# CitizenBoard_V3_2.net
KiCad netlist of a schematic drawn in EAGLE
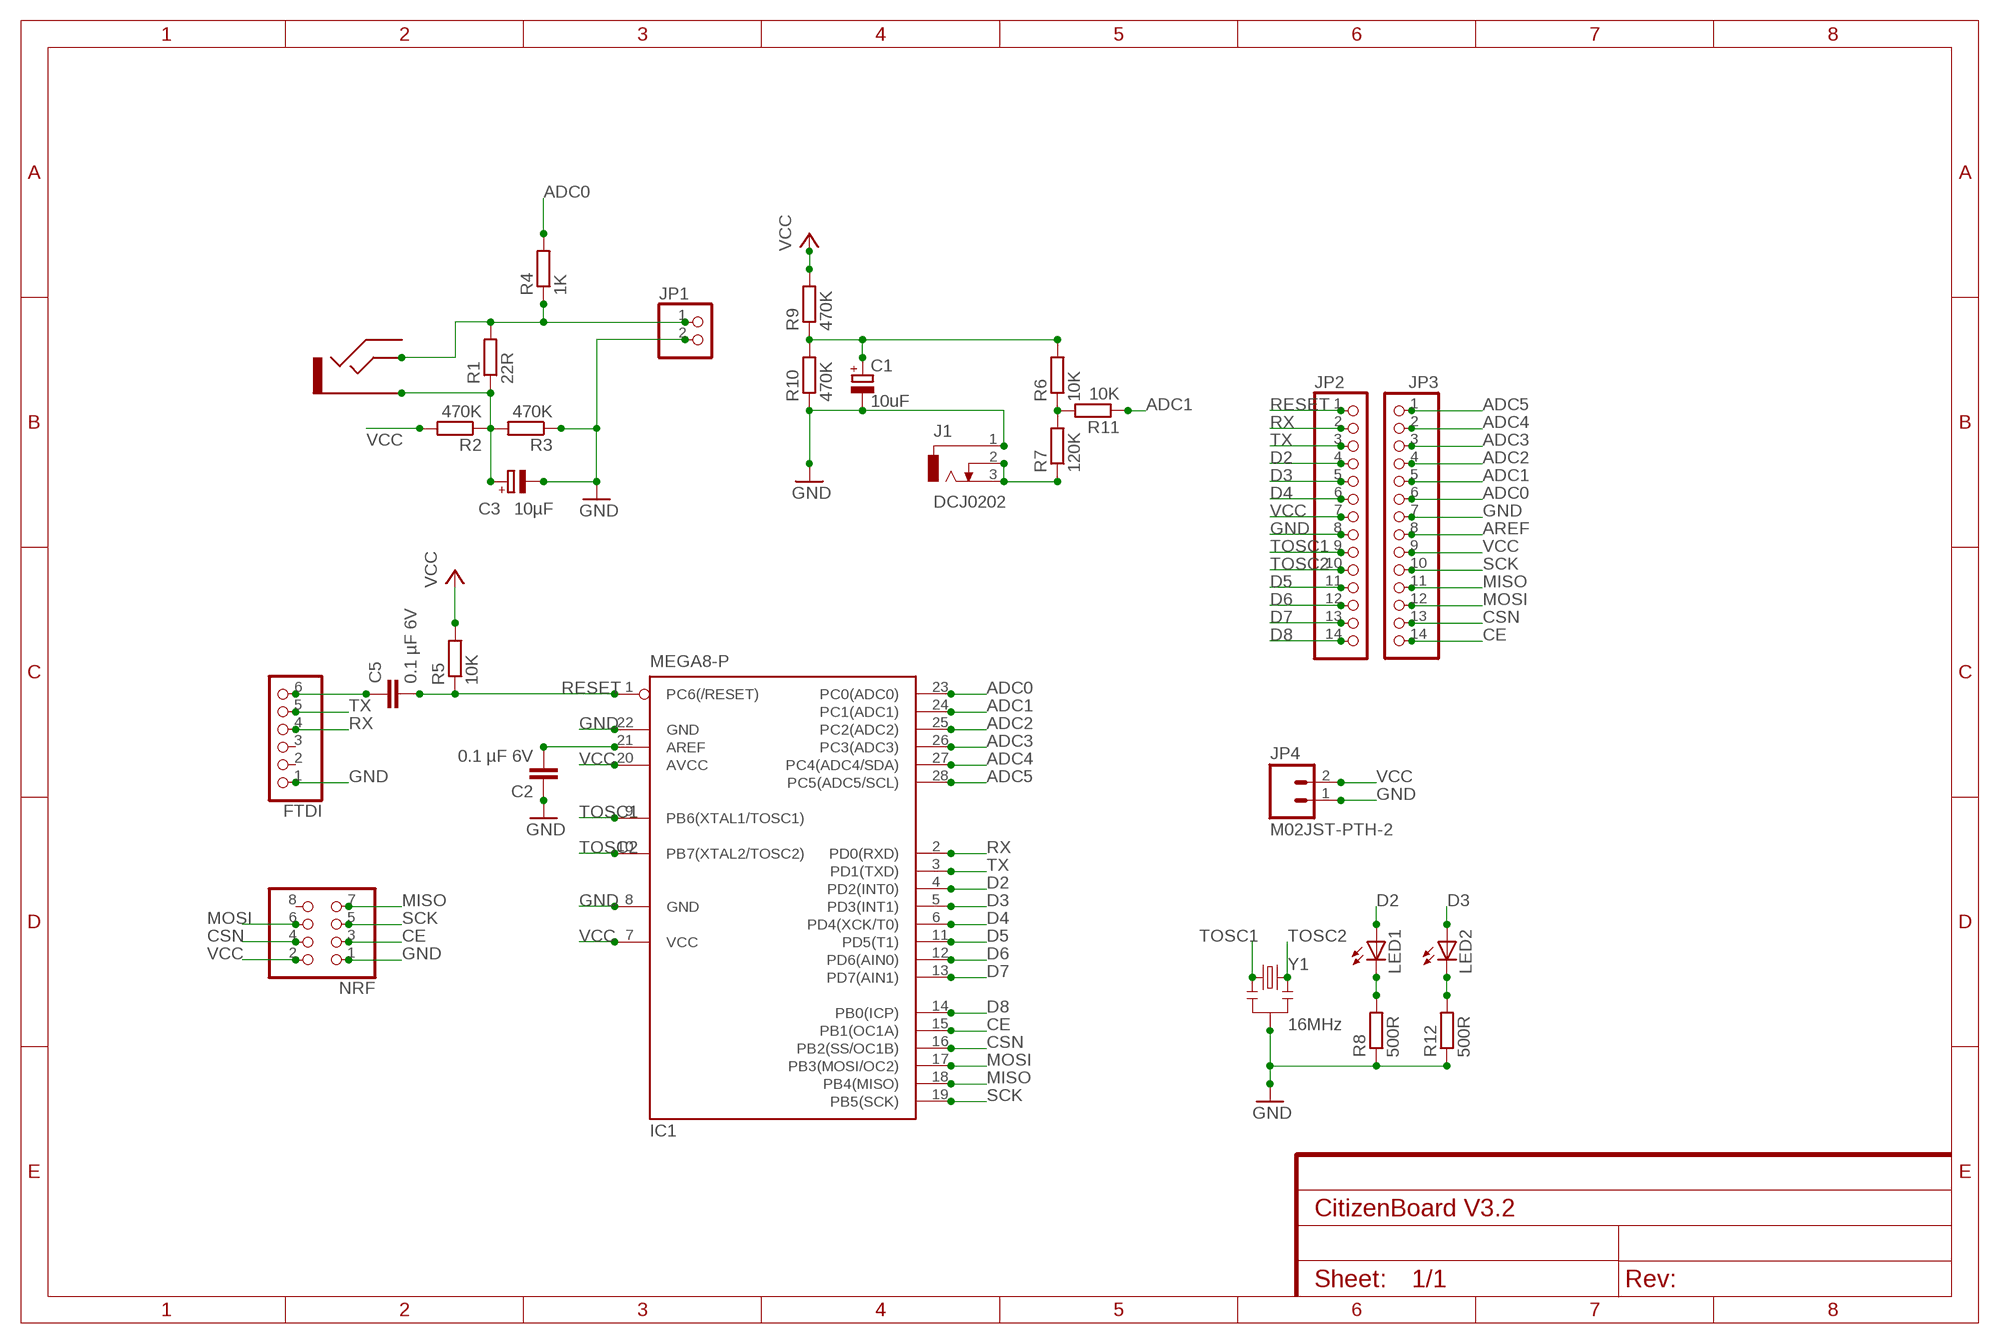
[diagram p0: schematic, sheet 1]

(export (version "E")
  (design (tool "Eeschema 10.0.6"))
  (components
    (comp (ref "C1")
      (value "10uF")
      (footprint "eagle-import:E2,5-6E")
      (libsource (lib "eagle-import") (part "CPOL-EUE2,5-6E"))
    )
    (comp (ref "C2")
      (value "0.1 µF 6V")
      (footprint "eagle-import:C025-024X044")
      (libsource (lib "eagle-import") (part "C-EU025-024X044"))
    )
    (comp (ref "C3")
      (value "10µF")
      (footprint "eagle-import:E2,5-6E")
      (libsource (lib "eagle-import") (part "CPOL-EUE2,5-6E"))
    )
    (comp (ref "C5")
      (value "0.1 µF 6V")
      (footprint "eagle-import:C025-024X044")
      (libsource (lib "eagle-import") (part "C-EU025-024X044"))
    )
    (comp (ref "FTDI")
      (value "PINHD-1X6")
      (footprint "eagle-import:1X06")
      (libsource (lib "eagle-import") (part "PINHD-1X6"))
    )
    (comp (ref "IC1")
      (value "MEGA8-P")
      (footprint "eagle-import:DIL28-3")
      (libsource (lib "eagle-import") (part "MEGA8-P"))
    )
    (comp (ref "J1")
      (value "DCJ0202")
      (footprint "eagle-import:DCJ0202")
      (libsource (lib "eagle-import") (part "DCJ0202"))
    )
    (comp (ref "J2")
      (value "AUDIO-JACK-3.5")
      (footprint "eagle-import:AUDIO-JACK-3.5")
      (libsource (lib "eagle-import") (part "AUDIO-JACK-3.5"))
    )
    (comp (ref "JP1")
      (value "PINHD-1X2")
      (footprint "eagle-import:1X02")
      (libsource (lib "eagle-import") (part "PINHD-1X2"))
    )
    (comp (ref "JP2")
      (value "PINHD-1X14")
      (footprint "eagle-import:1X14")
      (libsource (lib "eagle-import") (part "PINHD-1X14"))
    )
    (comp (ref "JP3")
      (value "PINHD-1X14")
      (footprint "eagle-import:1X14")
      (libsource (lib "eagle-import") (part "PINHD-1X14"))
    )
    (comp (ref "JP4")
      (value "M02JST-PTH-2")
      (footprint "eagle-import:JST-2-PTH")
      (libsource (lib "eagle-import") (part "M02JST-PTH-2"))
    )
    (comp (ref "LED1")
      (value "LED3MM")
      (footprint "eagle-import:LED3MM")
      (libsource (lib "eagle-import") (part "LED3MM"))
    )
    (comp (ref "LED2")
      (value "LED3MM")
      (footprint "eagle-import:LED3MM")
      (libsource (lib "eagle-import") (part "LED3MM"))
    )
    (comp (ref "NRF")
      (value "PINHD-2X4")
      (footprint "eagle-import:2X04")
      (libsource (lib "eagle-import") (part "PINHD-2X4"))
    )
    (comp (ref "R1")
      (value "22R")
      (footprint "eagle-import:0204_7")
      (libsource (lib "eagle-import") (part "R-EU_0204/7"))
    )
    (comp (ref "R2")
      (value "470K")
      (footprint "eagle-import:0204_7")
      (libsource (lib "eagle-import") (part "R-EU_0204/7"))
    )
    (comp (ref "R3")
      (value "470K")
      (footprint "eagle-import:0204_7")
      (libsource (lib "eagle-import") (part "R-EU_0204/7"))
    )
    (comp (ref "R4")
      (value "1K")
      (footprint "eagle-import:0204_7")
      (libsource (lib "eagle-import") (part "R-EU_0204/7"))
    )
    (comp (ref "R5")
      (value "10K")
      (footprint "eagle-import:0204_7")
      (libsource (lib "eagle-import") (part "R-EU_0204/7"))
    )
    (comp (ref "R6")
      (value "10K")
      (footprint "eagle-import:0204_7")
      (libsource (lib "eagle-import") (part "R-EU_0204/7"))
    )
    (comp (ref "R7")
      (value "120K")
      (footprint "eagle-import:0204_7")
      (libsource (lib "eagle-import") (part "R-EU_0204/7"))
    )
    (comp (ref "R8")
      (value "500R")
      (footprint "eagle-import:0204_7")
      (libsource (lib "eagle-import") (part "R-EU_0204/7"))
    )
    (comp (ref "R9")
      (value "470K")
      (footprint "eagle-import:0204_7")
      (libsource (lib "eagle-import") (part "R-EU_0204/7"))
    )
    (comp (ref "R10")
      (value "470K")
      (footprint "eagle-import:0204_7")
      (libsource (lib "eagle-import") (part "R-EU_0204/7"))
    )
    (comp (ref "R11")
      (value "10K")
      (footprint "eagle-import:0204_7")
      (libsource (lib "eagle-import") (part "R-EU_0204/7"))
    )
    (comp (ref "R12")
      (value "500R")
      (footprint "eagle-import:0204_7")
      (libsource (lib "eagle-import") (part "R-EU_0204/7"))
    )
    (comp (ref "Y1")
      (value "16MHz")
      (footprint "eagle-import:RESONATOR-PTH")
      (libsource (lib "eagle-import") (part "RESONATORPTH"))
    )
  )
  (nets
    (net (code "1") (name "/ADC0") (class "Default")
      (node (ref "IC1") (pin "23") (pinfunction "PC0(ADC0)_23") (pintype "bidirectional"))
      (node (ref "JP3") (pin "6") (pinfunction "6_6") (pintype "passive"))
      (node (ref "R4") (pin "2") (pinfunction "2_2") (pintype "passive"))
    )
    (net (code "2") (name "/ADC1") (class "Default")
      (node (ref "IC1") (pin "24") (pinfunction "PC1(ADC1)_24") (pintype "bidirectional"))
      (node (ref "JP3") (pin "5") (pinfunction "5_5") (pintype "passive"))
      (node (ref "R11") (pin "1") (pinfunction "1_1") (pintype "passive"))
    )
    (net (code "3") (name "/ADC2") (class "Default")
      (node (ref "IC1") (pin "25") (pinfunction "PC2(ADC2)_25") (pintype "bidirectional"))
      (node (ref "JP3") (pin "4") (pinfunction "4_4") (pintype "passive"))
    )
    (net (code "4") (name "/ADC3") (class "Default")
      (node (ref "IC1") (pin "26") (pinfunction "PC3(ADC3)_26") (pintype "bidirectional"))
      (node (ref "JP3") (pin "3") (pinfunction "3_3") (pintype "passive"))
    )
    (net (code "5") (name "/ADC4") (class "Default")
      (node (ref "IC1") (pin "27") (pinfunction "PC4(ADC4/SDA)_27") (pintype "bidirectional"))
      (node (ref "JP3") (pin "2") (pinfunction "2_2") (pintype "passive"))
    )
    (net (code "6") (name "/ADC5") (class "Default")
      (node (ref "IC1") (pin "28") (pinfunction "PC5(ADC5/SCL)_28") (pintype "bidirectional"))
      (node (ref "JP3") (pin "1") (pinfunction "1_1") (pintype "passive"))
    )
    (net (code "7") (name "/AREF") (class "Default")
      (node (ref "C2") (pin "2") (pinfunction "2_2") (pintype "passive"))
      (node (ref "IC1") (pin "21") (pinfunction "AREF_21") (pintype "passive"))
      (node (ref "JP3") (pin "8") (pinfunction "8_8") (pintype "passive"))
    )
    (net (code "8") (name "/CE") (class "Default")
      (node (ref "IC1") (pin "15") (pinfunction "PB1(OC1A)_15") (pintype "bidirectional"))
      (node (ref "JP3") (pin "14") (pinfunction "14_14") (pintype "passive"))
      (node (ref "NRF") (pin "3") (pinfunction "3_3") (pintype "passive"))
    )
    (net (code "9") (name "/CSN") (class "Default")
      (node (ref "IC1") (pin "16") (pinfunction "PB2(SS/OC1B)_16") (pintype "bidirectional"))
      (node (ref "JP3") (pin "13") (pinfunction "13_13") (pintype "passive"))
      (node (ref "NRF") (pin "4") (pinfunction "4_4") (pintype "passive"))
    )
    (net (code "10") (name "/D2") (class "Default")
      (node (ref "IC1") (pin "4") (pinfunction "PD2(INT0)_4") (pintype "bidirectional"))
      (node (ref "JP2") (pin "4") (pinfunction "4_4") (pintype "passive"))
      (node (ref "LED1") (pin "A") (pinfunction "A_A") (pintype "passive"))
    )
    (net (code "11") (name "/D3") (class "Default")
      (node (ref "IC1") (pin "5") (pinfunction "PD3(INT1)_5") (pintype "bidirectional"))
      (node (ref "JP2") (pin "5") (pinfunction "5_5") (pintype "passive"))
      (node (ref "LED2") (pin "A") (pinfunction "A_A") (pintype "passive"))
    )
    (net (code "12") (name "/D4") (class "Default")
      (node (ref "IC1") (pin "6") (pinfunction "PD4(XCK/T0)_6") (pintype "bidirectional"))
      (node (ref "JP2") (pin "6") (pinfunction "6_6") (pintype "passive"))
    )
    (net (code "13") (name "/D5") (class "Default")
      (node (ref "IC1") (pin "11") (pinfunction "PD5(T1)_11") (pintype "bidirectional"))
      (node (ref "JP2") (pin "11") (pinfunction "11_11") (pintype "passive"))
    )
    (net (code "14") (name "/D6") (class "Default")
      (node (ref "IC1") (pin "12") (pinfunction "PD6(AIN0)_12") (pintype "bidirectional"))
      (node (ref "JP2") (pin "12") (pinfunction "12_12") (pintype "passive"))
    )
    (net (code "15") (name "/D7") (class "Default")
      (node (ref "IC1") (pin "13") (pinfunction "PD7(AIN1)_13") (pintype "bidirectional"))
      (node (ref "JP2") (pin "13") (pinfunction "13_13") (pintype "passive"))
    )
    (net (code "16") (name "/D8") (class "Default")
      (node (ref "IC1") (pin "14") (pinfunction "PB0(ICP)_14") (pintype "bidirectional"))
      (node (ref "JP2") (pin "14") (pinfunction "14_14") (pintype "passive"))
    )
    (net (code "17") (name "/MISO") (class "Default")
      (node (ref "IC1") (pin "18") (pinfunction "PB4(MISO)_18") (pintype "bidirectional"))
      (node (ref "JP3") (pin "11") (pinfunction "11_11") (pintype "passive"))
      (node (ref "NRF") (pin "7") (pinfunction "7_7") (pintype "passive"))
    )
    (net (code "18") (name "/MOSI") (class "Default")
      (node (ref "IC1") (pin "17") (pinfunction "PB3(MOSI/OC2)_17") (pintype "bidirectional"))
      (node (ref "JP3") (pin "12") (pinfunction "12_12") (pintype "passive"))
      (node (ref "NRF") (pin "6") (pinfunction "6_6") (pintype "passive"))
    )
    (net (code "19") (name "/RESET") (class "Default")
      (node (ref "C5") (pin "2") (pinfunction "2_2") (pintype "passive"))
      (node (ref "IC1") (pin "1") (pinfunction "PC6(/RESET)_1") (pintype "bidirectional"))
      (node (ref "JP2") (pin "1") (pinfunction "1_1") (pintype "passive"))
      (node (ref "R5") (pin "1") (pinfunction "1_1") (pintype "passive"))
    )
    (net (code "20") (name "/RX") (class "Default")
      (node (ref "FTDI") (pin "4") (pinfunction "4_4") (pintype "passive"))
      (node (ref "IC1") (pin "2") (pinfunction "PD0(RXD)_2") (pintype "bidirectional"))
      (node (ref "JP2") (pin "2") (pinfunction "2_2") (pintype "passive"))
    )
    (net (code "21") (name "/SCK") (class "Default")
      (node (ref "IC1") (pin "19") (pinfunction "PB5(SCK)_19") (pintype "bidirectional"))
      (node (ref "JP3") (pin "10") (pinfunction "10_10") (pintype "passive"))
      (node (ref "NRF") (pin "5") (pinfunction "5_5") (pintype "passive"))
    )
    (net (code "22") (name "/TOSC1") (class "Default")
      (node (ref "IC1") (pin "9") (pinfunction "PB6(XTAL1/TOSC1)_9") (pintype "bidirectional"))
      (node (ref "JP2") (pin "9") (pinfunction "9_9") (pintype "passive"))
      (node (ref "Y1") (pin "1") (pinfunction "1_1") (pintype "passive"))
    )
    (net (code "23") (name "/TOSC2") (class "Default")
      (node (ref "IC1") (pin "10") (pinfunction "PB7(XTAL2/TOSC2)_10") (pintype "bidirectional"))
      (node (ref "JP2") (pin "10") (pinfunction "10_10") (pintype "passive"))
      (node (ref "Y1") (pin "3") (pinfunction "3_3") (pintype "passive"))
    )
    (net (code "24") (name "/TX") (class "Default")
      (node (ref "FTDI") (pin "5") (pinfunction "5_5") (pintype "passive"))
      (node (ref "IC1") (pin "3") (pinfunction "PD1(TXD)_3") (pintype "bidirectional"))
      (node (ref "JP2") (pin "3") (pinfunction "3_3") (pintype "passive"))
    )
    (net (code "25") (name "GND") (class "Default")
      (node (ref "C1") (pin "-") (pinfunction "-_-") (pintype "passive"))
      (node (ref "C2") (pin "1") (pinfunction "1_1") (pintype "passive"))
      (node (ref "C3") (pin "-") (pinfunction "-_-") (pintype "passive"))
      (node (ref "FTDI") (pin "1") (pinfunction "1_1") (pintype "passive"))
      (node (ref "IC1") (pin "22") (pinfunction "GND_22") (pintype "power_in"))
      (node (ref "IC1") (pin "8") (pinfunction "GND_8") (pintype "power_in"))
      (node (ref "J1") (pin "1") (pinfunction "1_1") (pintype "passive"))
      (node (ref "JP1") (pin "2") (pinfunction "2_2") (pintype "passive"))
      (node (ref "JP2") (pin "8") (pinfunction "8_8") (pintype "passive"))
      (node (ref "JP3") (pin "7") (pinfunction "7_7") (pintype "passive"))
      (node (ref "JP4") (pin "1") (pinfunction "1_1") (pintype "passive"))
      (node (ref "NRF") (pin "1") (pinfunction "1_1") (pintype "passive"))
      (node (ref "R10") (pin "1") (pinfunction "1_1") (pintype "passive"))
      (node (ref "R12") (pin "1") (pinfunction "1_1") (pintype "passive"))
      (node (ref "R3") (pin "1") (pinfunction "1_1") (pintype "passive"))
      (node (ref "R8") (pin "1") (pinfunction "1_1") (pintype "passive"))
      (node (ref "Y1") (pin "2") (pinfunction "2_2") (pintype "passive"))
    )
    (net (code "26") (name "Net-(C1-Pad+)") (class "Default")
      (node (ref "C1") (pin "+") (pinfunction "+_+") (pintype "passive"))
      (node (ref "R10") (pin "2") (pinfunction "2_2") (pintype "passive"))
      (node (ref "R6") (pin "2") (pinfunction "2_2") (pintype "passive"))
      (node (ref "R9") (pin "1") (pinfunction "1_1") (pintype "passive"))
    )
    (net (code "27") (name "Net-(C5-Pad1)") (class "Default")
      (node (ref "C5") (pin "1") (pinfunction "1_1") (pintype "passive"))
      (node (ref "FTDI") (pin "6") (pinfunction "6_6") (pintype "passive"))
    )
    (net (code "28") (name "Net-(J1-Pad2)") (class "Default")
      (node (ref "J1") (pin "2") (pinfunction "2_2") (pintype "passive"))
      (node (ref "J1") (pin "3") (pinfunction "3_3") (pintype "passive"))
      (node (ref "R7") (pin "1") (pinfunction "1_1") (pintype "passive"))
    )
    (net (code "29") (name "Net-(J2-GND)") (class "Default")
      (node (ref "C3") (pin "+") (pinfunction "+_+") (pintype "passive"))
      (node (ref "J2") (pin "1S") (pinfunction "GND_1S") (pintype "bidirectional"))
      (node (ref "R1") (pin "1") (pinfunction "1_1") (pintype "passive"))
      (node (ref "R2") (pin "1") (pinfunction "1_1") (pintype "passive"))
      (node (ref "R3") (pin "2") (pinfunction "2_2") (pintype "passive"))
    )
    (net (code "30") (name "Net-(J2-L)") (class "Default")
      (node (ref "J2") (pin "5T") (pinfunction "L_5T") (pintype "bidirectional"))
      (node (ref "JP1") (pin "1") (pinfunction "1_1") (pintype "passive"))
      (node (ref "R1") (pin "2") (pinfunction "2_2") (pintype "passive"))
      (node (ref "R4") (pin "1") (pinfunction "1_1") (pintype "passive"))
    )
    (net (code "31") (name "Net-(LED1-C)") (class "Default")
      (node (ref "LED1") (pin "K") (pinfunction "C_K") (pintype "passive"))
      (node (ref "R8") (pin "2") (pinfunction "2_2") (pintype "passive"))
    )
    (net (code "32") (name "Net-(LED2-C)") (class "Default")
      (node (ref "LED2") (pin "K") (pinfunction "C_K") (pintype "passive"))
      (node (ref "R12") (pin "2") (pinfunction "2_2") (pintype "passive"))
    )
    (net (code "33") (name "Net-(R11-Pad2)") (class "Default")
      (node (ref "R11") (pin "2") (pinfunction "2_2") (pintype "passive"))
      (node (ref "R6") (pin "1") (pinfunction "1_1") (pintype "passive"))
      (node (ref "R7") (pin "2") (pinfunction "2_2") (pintype "passive"))
    )
    (net (code "34") (name "VCC") (class "Default")
      (node (ref "IC1") (pin "20") (pinfunction "AVCC_20") (pintype "power_in"))
      (node (ref "IC1") (pin "7") (pinfunction "VCC_7") (pintype "power_in"))
      (node (ref "JP2") (pin "7") (pinfunction "7_7") (pintype "passive"))
      (node (ref "JP3") (pin "9") (pinfunction "9_9") (pintype "passive"))
      (node (ref "JP4") (pin "2") (pinfunction "2_2") (pintype "passive"))
      (node (ref "NRF") (pin "2") (pinfunction "2_2") (pintype "passive"))
      (node (ref "R2") (pin "2") (pinfunction "2_2") (pintype "passive"))
      (node (ref "R5") (pin "2") (pinfunction "2_2") (pintype "passive"))
      (node (ref "R9") (pin "2") (pinfunction "2_2") (pintype "passive"))
    )
    (net (code "35") (name "unconnected-(FTDI-Pad2)") (class "Default")
      (node (ref "FTDI") (pin "2") (pinfunction "2_2") (pintype "passive"))
    )
    (net (code "36") (name "unconnected-(FTDI-Pad3)") (class "Default")
      (node (ref "FTDI") (pin "3") (pinfunction "3_3") (pintype "passive"))
    )
    (net (code "37") (name "unconnected-(J2-R-Pad2R)") (class "Default")
      (node (ref "J2") (pin "2R") (pinfunction "R_2R") (pintype "bidirectional"))
    )
    (net (code "38") (name "unconnected-(NRF-Pad8)") (class "Default")
      (node (ref "NRF") (pin "8") (pinfunction "8_8") (pintype "passive"))
    )
  )
)
